# DoomPlayer.net
KiCad netlist of a schematic drawn in EAGLE
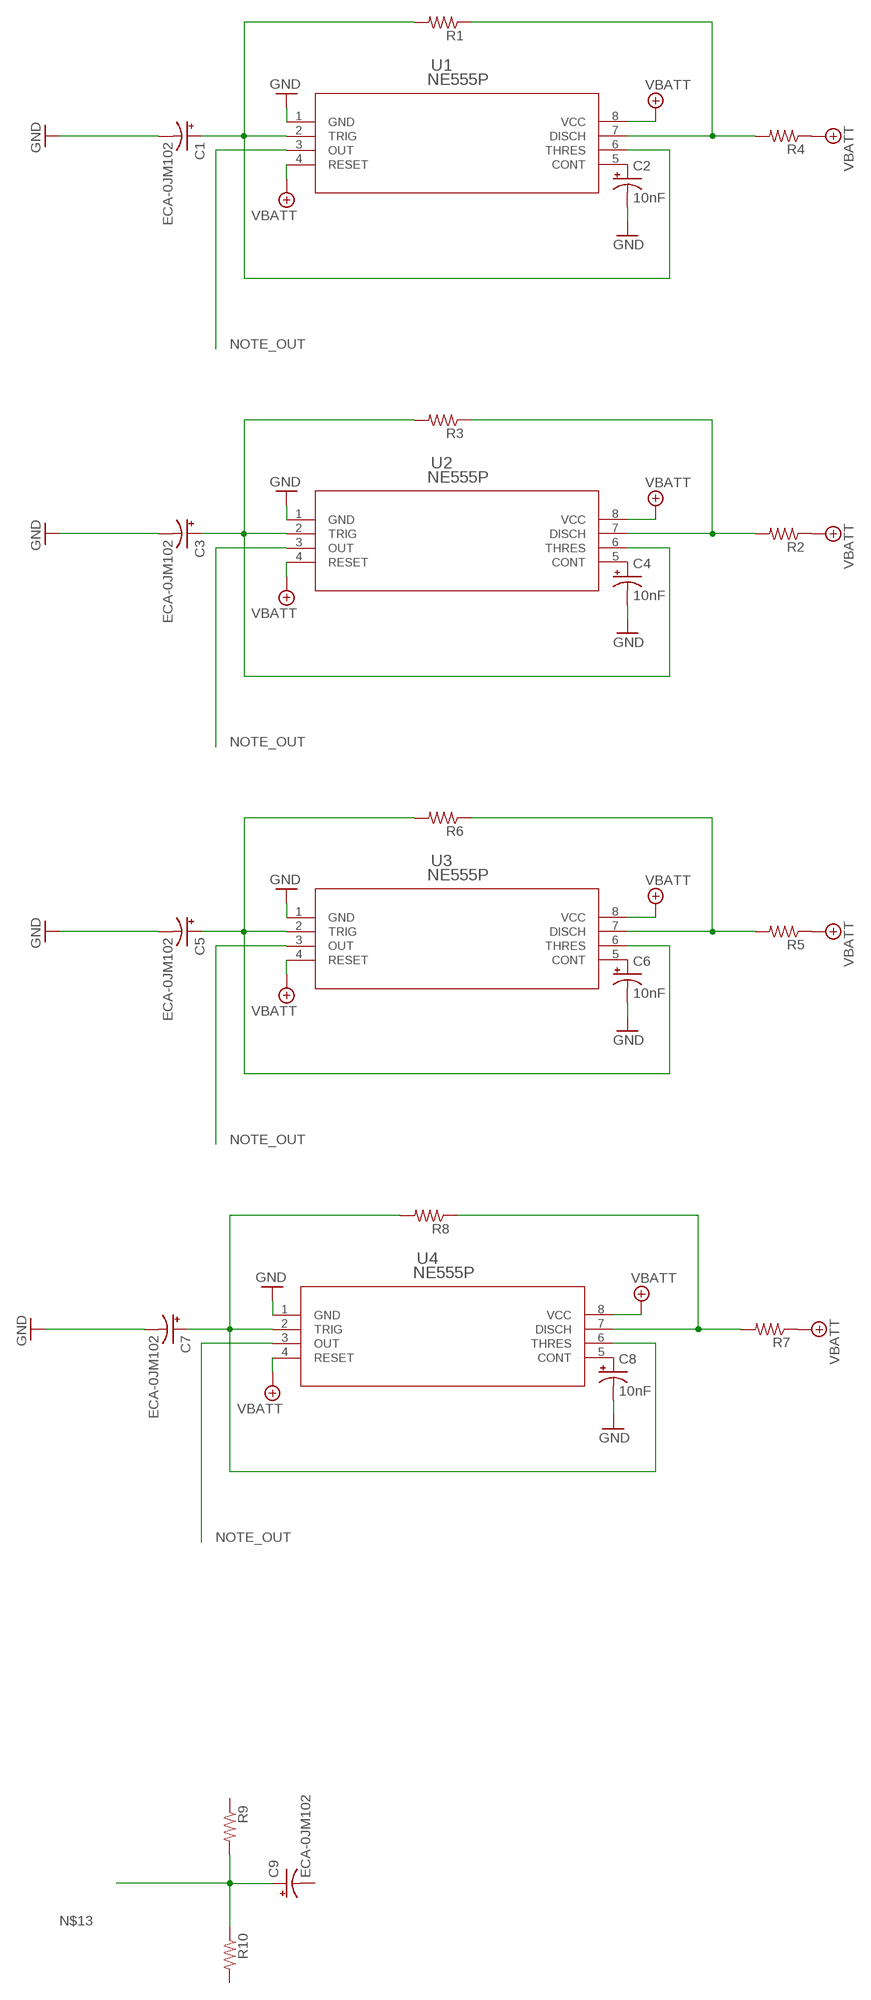
[diagram p0: schematic, sheet 1]

(export (version "E")
  (design (tool "Eeschema 10.0.6"))
  (components
    (comp (ref "C1")
      (value "ECA-0JM102")
      (footprint "eagle-import:PCAP_8X112")
      (fields (field (name "MANUFACTURER_PART_NUMBER") "ECA0JM102"))
      (libsource (lib "eagle-import") (part "ECA-0JM102"))
    )
    (comp (ref "C2")
      (value "10nF")
      (footprint "eagle-import:PCAP_8X112")
      (fields (field (name "MANUFACTURER_PART_NUMBER") "ECA0JM102"))
      (libsource (lib "eagle-import") (part "ECA-0JM102"))
    )
    (comp (ref "C3")
      (value "ECA-0JM102")
      (footprint "eagle-import:PCAP_8X112")
      (fields (field (name "MANUFACTURER_PART_NUMBER") "ECA0JM102"))
      (libsource (lib "eagle-import") (part "ECA-0JM102"))
    )
    (comp (ref "C4")
      (value "10nF")
      (footprint "eagle-import:PCAP_8X112")
      (fields (field (name "MANUFACTURER_PART_NUMBER") "ECA0JM102"))
      (libsource (lib "eagle-import") (part "ECA-0JM102"))
    )
    (comp (ref "C5")
      (value "ECA-0JM102")
      (footprint "eagle-import:PCAP_8X112")
      (fields (field (name "MANUFACTURER_PART_NUMBER") "ECA0JM102"))
      (libsource (lib "eagle-import") (part "ECA-0JM102"))
    )
    (comp (ref "C6")
      (value "10nF")
      (footprint "eagle-import:PCAP_8X112")
      (fields (field (name "MANUFACTURER_PART_NUMBER") "ECA0JM102"))
      (libsource (lib "eagle-import") (part "ECA-0JM102"))
    )
    (comp (ref "C7")
      (value "ECA-0JM102")
      (footprint "eagle-import:PCAP_8X112")
      (fields (field (name "MANUFACTURER_PART_NUMBER") "ECA0JM102"))
      (libsource (lib "eagle-import") (part "ECA-0JM102"))
    )
    (comp (ref "C8")
      (value "10nF")
      (footprint "eagle-import:PCAP_8X112")
      (fields (field (name "MANUFACTURER_PART_NUMBER") "ECA0JM102"))
      (libsource (lib "eagle-import") (part "ECA-0JM102"))
    )
    (comp (ref "C9")
      (value "ECA-0JM102")
      (footprint "eagle-import:PCAP_8X112")
      (fields (field (name "MANUFACTURER_PART_NUMBER") "ECA0JM102"))
      (libsource (lib "eagle-import") (part "ECA-0JM102"))
    )
    (comp (ref "R1")
      (value "ERJ-L06KF50MV")
      (footprint "eagle-import:RC0805N")
      (libsource (lib "eagle-import") (part "ERJ-L06KF50MV"))
    )
    (comp (ref "R2")
      (value "ERJ-L06KF50MV")
      (footprint "eagle-import:RC0805N")
      (libsource (lib "eagle-import") (part "ERJ-L06KF50MV"))
    )
    (comp (ref "R3")
      (value "ERJ-L06KF50MV")
      (footprint "eagle-import:RC0805N")
      (libsource (lib "eagle-import") (part "ERJ-L06KF50MV"))
    )
    (comp (ref "R4")
      (value "ERJ-L06KF50MV")
      (footprint "eagle-import:RC0805N")
      (libsource (lib "eagle-import") (part "ERJ-L06KF50MV"))
    )
    (comp (ref "R5")
      (value "ERJ-L06KF50MV")
      (footprint "eagle-import:RC0805N")
      (libsource (lib "eagle-import") (part "ERJ-L06KF50MV"))
    )
    (comp (ref "R6")
      (value "ERJ-L06KF50MV")
      (footprint "eagle-import:RC0805N")
      (libsource (lib "eagle-import") (part "ERJ-L06KF50MV"))
    )
    (comp (ref "R7")
      (value "ERJ-L06KF50MV")
      (footprint "eagle-import:RC0805N")
      (libsource (lib "eagle-import") (part "ERJ-L06KF50MV"))
    )
    (comp (ref "R8")
      (value "ERJ-L06KF50MV")
      (footprint "eagle-import:RC0805N")
      (libsource (lib "eagle-import") (part "ERJ-L06KF50MV"))
    )
    (comp (ref "R9")
      (value "ERJ-L06KF50MV")
      (footprint "eagle-import:RC0805N")
      (libsource (lib "eagle-import") (part "ERJ-L06KF50MV"))
    )
    (comp (ref "R10")
      (value "ERJ-L06KF50MV")
      (footprint "eagle-import:RC0805N")
      (libsource (lib "eagle-import") (part "ERJ-L06KF50MV"))
    )
    (comp (ref "U1")
      (value "NE555P")
      (footprint "eagle-import:P8")
      (fields (field (name "GENERIC_PART_NUMBER") "NE555") (field (name "MANUFACTURER") "Texas Instruments"))
      (libsource (lib "eagle-import") (part "NE555P"))
    )
    (comp (ref "U2")
      (value "NE555P")
      (footprint "eagle-import:P8")
      (fields (field (name "GENERIC_PART_NUMBER") "NE555") (field (name "MANUFACTURER") "Texas Instruments"))
      (libsource (lib "eagle-import") (part "NE555P"))
    )
    (comp (ref "U3")
      (value "NE555P")
      (footprint "eagle-import:P8")
      (fields (field (name "GENERIC_PART_NUMBER") "NE555") (field (name "MANUFACTURER") "Texas Instruments"))
      (libsource (lib "eagle-import") (part "NE555P"))
    )
    (comp (ref "U4")
      (value "NE555P")
      (footprint "eagle-import:P8")
      (fields (field (name "GENERIC_PART_NUMBER") "NE555") (field (name "MANUFACTURER") "Texas Instruments"))
      (libsource (lib "eagle-import") (part "NE555P"))
    )
  )
  (nets
    (net (code "1") (name "/N$13") (class "Default")
      (node (ref "C9") (pin "1") (pinfunction "+_1") (pintype "passive"))
      (node (ref "R10") (pin "1") (pinfunction "PIN1_1") (pintype "passive"))
      (node (ref "R9") (pin "2") (pinfunction "PIN2_2") (pintype "passive"))
    )
    (net (code "2") (name "/NOTE_OUT") (class "Default")
      (node (ref "U1") (pin "3") (pinfunction "OUT_3") (pintype "output"))
      (node (ref "U2") (pin "3") (pinfunction "OUT_3") (pintype "output"))
      (node (ref "U3") (pin "3") (pinfunction "OUT_3") (pintype "output"))
      (node (ref "U4") (pin "3") (pinfunction "OUT_3") (pintype "output"))
    )
    (net (code "3") (name "GND") (class "Default")
      (node (ref "C1") (pin "2") (pinfunction "-_2") (pintype "passive"))
      (node (ref "C2") (pin "2") (pinfunction "-_2") (pintype "passive"))
      (node (ref "C3") (pin "2") (pinfunction "-_2") (pintype "passive"))
      (node (ref "C4") (pin "2") (pinfunction "-_2") (pintype "passive"))
      (node (ref "C5") (pin "2") (pinfunction "-_2") (pintype "passive"))
      (node (ref "C6") (pin "2") (pinfunction "-_2") (pintype "passive"))
      (node (ref "C7") (pin "2") (pinfunction "-_2") (pintype "passive"))
      (node (ref "C8") (pin "2") (pinfunction "-_2") (pintype "passive"))
      (node (ref "U1") (pin "1") (pinfunction "GND_1") (pintype "power_in"))
      (node (ref "U2") (pin "1") (pinfunction "GND_1") (pintype "power_in"))
      (node (ref "U3") (pin "1") (pinfunction "GND_1") (pintype "power_in"))
      (node (ref "U4") (pin "1") (pinfunction "GND_1") (pintype "power_in"))
    )
    (net (code "4") (name "Net-(C1-+)") (class "Default")
      (node (ref "C1") (pin "1") (pinfunction "+_1") (pintype "passive"))
      (node (ref "R1") (pin "2") (pinfunction "PIN2_2") (pintype "passive"))
      (node (ref "U1") (pin "2") (pinfunction "TRIG_2") (pintype "input"))
      (node (ref "U1") (pin "6") (pinfunction "THRES_6") (pintype "input"))
    )
    (net (code "5") (name "Net-(C2-+)") (class "Default")
      (node (ref "C2") (pin "1") (pinfunction "+_1") (pintype "passive"))
      (node (ref "U1") (pin "5") (pinfunction "CONT_5") (pintype "passive"))
    )
    (net (code "6") (name "Net-(C3-+)") (class "Default")
      (node (ref "C3") (pin "1") (pinfunction "+_1") (pintype "passive"))
      (node (ref "R3") (pin "2") (pinfunction "PIN2_2") (pintype "passive"))
      (node (ref "U2") (pin "2") (pinfunction "TRIG_2") (pintype "input"))
      (node (ref "U2") (pin "6") (pinfunction "THRES_6") (pintype "input"))
    )
    (net (code "7") (name "Net-(C4-+)") (class "Default")
      (node (ref "C4") (pin "1") (pinfunction "+_1") (pintype "passive"))
      (node (ref "U2") (pin "5") (pinfunction "CONT_5") (pintype "passive"))
    )
    (net (code "8") (name "Net-(C5-+)") (class "Default")
      (node (ref "C5") (pin "1") (pinfunction "+_1") (pintype "passive"))
      (node (ref "R6") (pin "2") (pinfunction "PIN2_2") (pintype "passive"))
      (node (ref "U3") (pin "2") (pinfunction "TRIG_2") (pintype "input"))
      (node (ref "U3") (pin "6") (pinfunction "THRES_6") (pintype "input"))
    )
    (net (code "9") (name "Net-(C6-+)") (class "Default")
      (node (ref "C6") (pin "1") (pinfunction "+_1") (pintype "passive"))
      (node (ref "U3") (pin "5") (pinfunction "CONT_5") (pintype "passive"))
    )
    (net (code "10") (name "Net-(C7-+)") (class "Default")
      (node (ref "C7") (pin "1") (pinfunction "+_1") (pintype "passive"))
      (node (ref "R8") (pin "2") (pinfunction "PIN2_2") (pintype "passive"))
      (node (ref "U4") (pin "2") (pinfunction "TRIG_2") (pintype "input"))
      (node (ref "U4") (pin "6") (pinfunction "THRES_6") (pintype "input"))
    )
    (net (code "11") (name "Net-(C8-+)") (class "Default")
      (node (ref "C8") (pin "1") (pinfunction "+_1") (pintype "passive"))
      (node (ref "U4") (pin "5") (pinfunction "CONT_5") (pintype "passive"))
    )
    (net (code "12") (name "Net-(R1-PIN1)") (class "Default")
      (node (ref "R1") (pin "1") (pinfunction "PIN1_1") (pintype "passive"))
      (node (ref "R4") (pin "2") (pinfunction "PIN2_2") (pintype "passive"))
      (node (ref "U1") (pin "7") (pinfunction "DISCH_7") (pintype "passive"))
    )
    (net (code "13") (name "Net-(R2-PIN2)") (class "Default")
      (node (ref "R2") (pin "2") (pinfunction "PIN2_2") (pintype "passive"))
      (node (ref "R3") (pin "1") (pinfunction "PIN1_1") (pintype "passive"))
      (node (ref "U2") (pin "7") (pinfunction "DISCH_7") (pintype "passive"))
    )
    (net (code "14") (name "Net-(R5-PIN2)") (class "Default")
      (node (ref "R5") (pin "2") (pinfunction "PIN2_2") (pintype "passive"))
      (node (ref "R6") (pin "1") (pinfunction "PIN1_1") (pintype "passive"))
      (node (ref "U3") (pin "7") (pinfunction "DISCH_7") (pintype "passive"))
    )
    (net (code "15") (name "Net-(R7-PIN2)") (class "Default")
      (node (ref "R7") (pin "2") (pinfunction "PIN2_2") (pintype "passive"))
      (node (ref "R8") (pin "1") (pinfunction "PIN1_1") (pintype "passive"))
      (node (ref "U4") (pin "7") (pinfunction "DISCH_7") (pintype "passive"))
    )
    (net (code "16") (name "VBATT") (class "Default")
      (node (ref "R2") (pin "1") (pinfunction "PIN1_1") (pintype "passive"))
      (node (ref "R4") (pin "1") (pinfunction "PIN1_1") (pintype "passive"))
      (node (ref "R5") (pin "1") (pinfunction "PIN1_1") (pintype "passive"))
      (node (ref "R7") (pin "1") (pinfunction "PIN1_1") (pintype "passive"))
      (node (ref "U1") (pin "4") (pinfunction "RESET_4") (pintype "input"))
      (node (ref "U1") (pin "8") (pinfunction "VCC_8") (pintype "power_in"))
      (node (ref "U2") (pin "4") (pinfunction "RESET_4") (pintype "input"))
      (node (ref "U2") (pin "8") (pinfunction "VCC_8") (pintype "power_in"))
      (node (ref "U3") (pin "4") (pinfunction "RESET_4") (pintype "input"))
      (node (ref "U3") (pin "8") (pinfunction "VCC_8") (pintype "power_in"))
      (node (ref "U4") (pin "4") (pinfunction "RESET_4") (pintype "input"))
      (node (ref "U4") (pin "8") (pinfunction "VCC_8") (pintype "power_in"))
    )
    (net (code "17") (name "unconnected-(C9---Pad2)") (class "Default")
      (node (ref "C9") (pin "2") (pinfunction "-_2") (pintype "passive"))
    )
    (net (code "18") (name "unconnected-(R9-PIN1-Pad1)") (class "Default")
      (node (ref "R9") (pin "1") (pinfunction "PIN1_1") (pintype "passive"))
    )
    (net (code "19") (name "unconnected-(R10-PIN2-Pad2)") (class "Default")
      (node (ref "R10") (pin "2") (pinfunction "PIN2_2") (pintype "passive"))
    )
  )
)
